# 07-MISC.net
KiCad netlist of a schematic drawn in Altium Designer
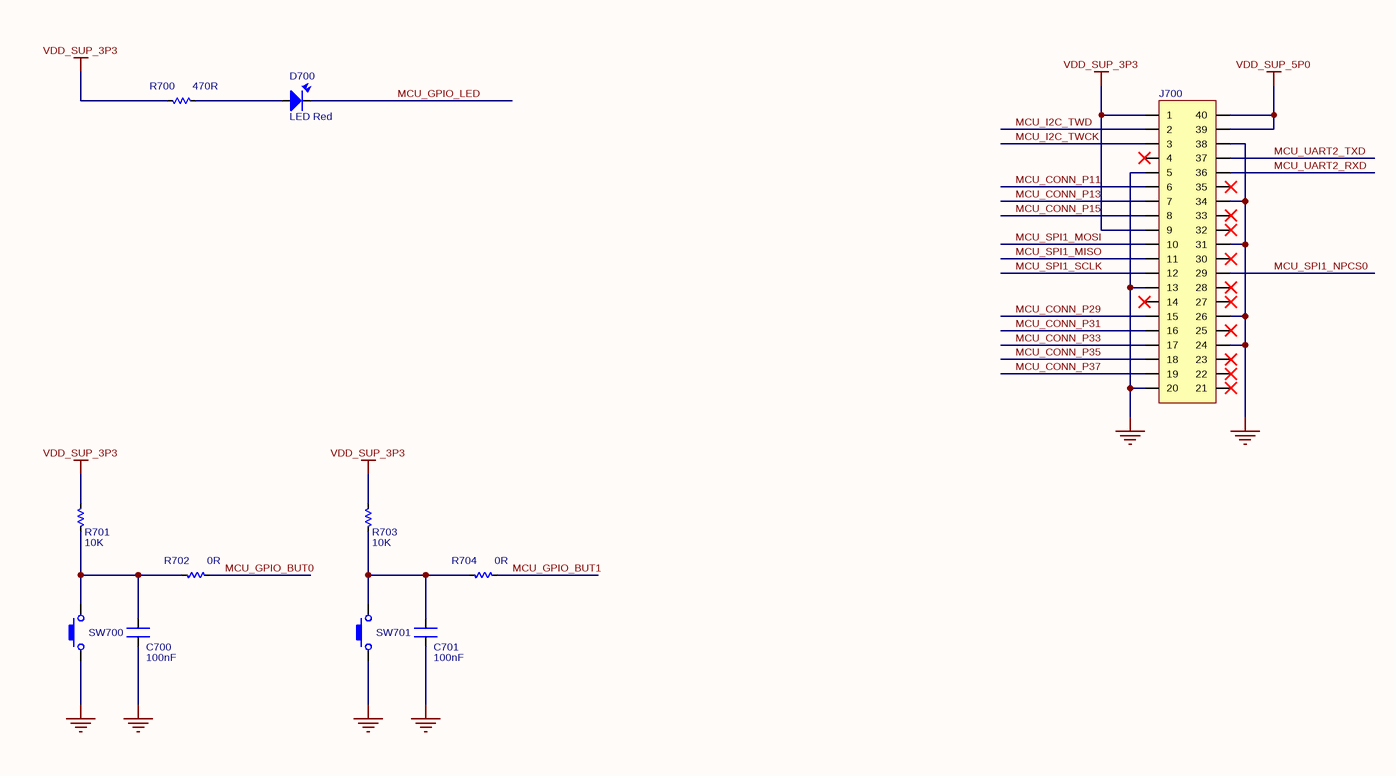
[diagram p0: 07-MISC.SchDoc]

(export (version "E")
  (design (tool "Eeschema 10.0.6"))
  (components
    (comp (ref "C700")
      (value "100nF")
      (footprint "CN-SMD-0603")
      (description "Ceramic Capacitor SMD 0603 100nF ±20% 10V")
      (fields (field (name "Comment") "Capacitor"))
      (libsource (lib "AS50") (part "Cap"))
    )
    (comp (ref "C701")
      (value "100nF")
      (footprint "CN-SMD-0603")
      (description "Ceramic Capacitor SMD 0603 100nF ±20% 10V")
      (fields (field (name "Comment") "Capacitor"))
      (libsource (lib "AS50") (part "Cap"))
    )
    (comp (ref "D700")
      (value "LED Red")
      (footprint "LED-SMD-0805-RED")
      (description "Light Emitting Diode SMD 0805 red color")
      (libsource (lib "AS50") (part "LED"))
    )
    (comp (ref "J700")
      (value "JP20x2")
      (footprint "JP20-D2T")
      (description "Double 20-pin jumper")
      (libsource (lib "AS50") (part "JP20x2"))
    )
    (comp (ref "R700")
      (value "470R")
      (footprint "RES-SMD-0603")
      (description "Resistor SMD 0603 470R 1% 0.1W")
      (fields (field (name "Comment") "Resistor"))
      (libsource (lib "AS50") (part "Res"))
    )
    (comp (ref "R701")
      (value "10K")
      (footprint "RES-SMD-0603")
      (description "Resistor SMD 0603 10K 1% 0.1W")
      (fields (field (name "Comment") "Resistor"))
      (libsource (lib "AS50") (part "Res"))
    )
    (comp (ref "R702")
      (value "0R")
      (footprint "RES-SMD-0603")
      (description "Resistor SMD 0603 0R 1% 0.1W")
      (fields (field (name "Comment") "Resistor"))
      (libsource (lib "AS50") (part "Res"))
    )
    (comp (ref "R703")
      (value "10K")
      (footprint "RES-SMD-0603")
      (description "Resistor SMD 0603 10K 1% 0.1W")
      (fields (field (name "Comment") "Resistor"))
      (libsource (lib "AS50") (part "Res"))
    )
    (comp (ref "R704")
      (value "0R")
      (footprint "RES-SMD-0603")
      (description "Resistor SMD 0603 0R 1% 0.1W")
      (fields (field (name "Comment") "Resistor"))
      (libsource (lib "AS50") (part "Res"))
    )
    (comp (ref "SW700")
      (value "SW2")
      (footprint "SW2-SMD-3x4x2M")
      (description "Switch 2-pin SMD 3x4x2mm")
      (libsource (lib "AS50") (part "SW2"))
    )
    (comp (ref "SW701")
      (value "SW2")
      (footprint "SW2-SMD-3x4x2M")
      (description "Switch 2-pin SMD 3x4x2mm")
      (libsource (lib "AS50") (part "SW2"))
    )
  )
  (nets
    (net (code "1") (name "/MCU_CONN_P11") (class "Default")
      (node (ref "J700") (pin "6") (pinfunction "6_6") (pintype "passive"))
    )
    (net (code "2") (name "/MCU_CONN_P13") (class "Default")
      (node (ref "J700") (pin "7") (pinfunction "7_7") (pintype "passive"))
    )
    (net (code "3") (name "/MCU_CONN_P15") (class "Default")
      (node (ref "J700") (pin "8") (pinfunction "8_8") (pintype "passive"))
    )
    (net (code "4") (name "/MCU_CONN_P29") (class "Default")
      (node (ref "J700") (pin "15") (pinfunction "15_15") (pintype "passive"))
    )
    (net (code "5") (name "/MCU_CONN_P31") (class "Default")
      (node (ref "J700") (pin "16") (pinfunction "16_16") (pintype "passive"))
    )
    (net (code "6") (name "/MCU_CONN_P33") (class "Default")
      (node (ref "J700") (pin "17") (pinfunction "17_17") (pintype "passive"))
    )
    (net (code "7") (name "/MCU_CONN_P35") (class "Default")
      (node (ref "J700") (pin "18") (pinfunction "18_18") (pintype "passive"))
    )
    (net (code "8") (name "/MCU_CONN_P37") (class "Default")
      (node (ref "J700") (pin "19") (pinfunction "19_19") (pintype "passive"))
    )
    (net (code "9") (name "/MCU_GPIO_BUT0") (class "Default")
      (node (ref "R702") (pin "2") (pinfunction "2_2") (pintype "passive"))
    )
    (net (code "10") (name "/MCU_GPIO_BUT1") (class "Default")
      (node (ref "R704") (pin "2") (pinfunction "2_2") (pintype "passive"))
    )
    (net (code "11") (name "/MCU_GPIO_LED") (class "Default")
      (node (ref "D700") (pin "2") (pinfunction "2_2") (pintype "passive"))
    )
    (net (code "12") (name "/MCU_I2C_TWCK") (class "Default")
      (node (ref "J700") (pin "3") (pinfunction "3_3") (pintype "passive"))
    )
    (net (code "13") (name "/MCU_I2C_TWD") (class "Default")
      (node (ref "J700") (pin "2") (pinfunction "2_2") (pintype "passive"))
    )
    (net (code "14") (name "/MCU_SPI1_MISO") (class "Default")
      (node (ref "J700") (pin "11") (pinfunction "11_11") (pintype "passive"))
    )
    (net (code "15") (name "/MCU_SPI1_MOSI") (class "Default")
      (node (ref "J700") (pin "10") (pinfunction "10_10") (pintype "passive"))
    )
    (net (code "16") (name "/MCU_SPI1_NPCS0") (class "Default")
      (node (ref "J700") (pin "29") (pinfunction "29_29") (pintype "passive"))
    )
    (net (code "17") (name "/MCU_SPI1_SCLK") (class "Default")
      (node (ref "J700") (pin "12") (pinfunction "12_12") (pintype "passive"))
    )
    (net (code "18") (name "/MCU_UART2_RXD") (class "Default")
      (node (ref "J700") (pin "36") (pinfunction "36_36") (pintype "passive"))
    )
    (net (code "19") (name "/MCU_UART2_TXD") (class "Default")
      (node (ref "J700") (pin "37") (pinfunction "37_37") (pintype "passive"))
    )
    (net (code "20") (name "GND") (class "Default")
      (node (ref "C700") (pin "1") (pinfunction "1_1") (pintype "passive"))
      (node (ref "C701") (pin "1") (pinfunction "1_1") (pintype "passive"))
      (node (ref "J700") (pin "13") (pinfunction "13_13") (pintype "passive"))
      (node (ref "J700") (pin "20") (pinfunction "20_20") (pintype "passive"))
      (node (ref "J700") (pin "24") (pinfunction "24_24") (pintype "passive"))
      (node (ref "J700") (pin "26") (pinfunction "26_26") (pintype "passive"))
      (node (ref "J700") (pin "31") (pinfunction "31_31") (pintype "passive"))
      (node (ref "J700") (pin "34") (pinfunction "34_34") (pintype "passive"))
      (node (ref "J700") (pin "38") (pinfunction "38_38") (pintype "passive"))
      (node (ref "J700") (pin "5") (pinfunction "5_5") (pintype "passive"))
      (node (ref "SW700") (pin "1") (pinfunction "1_1") (pintype "passive"))
      (node (ref "SW701") (pin "1") (pinfunction "1_1") (pintype "passive"))
    )
    (net (code "21") (name "Net-(C700-Pad2)") (class "Default")
      (node (ref "C700") (pin "2") (pinfunction "2_2") (pintype "passive"))
      (node (ref "R701") (pin "2") (pinfunction "2_2") (pintype "passive"))
      (node (ref "R702") (pin "1") (pinfunction "1_1") (pintype "passive"))
      (node (ref "SW700") (pin "2") (pinfunction "2_2") (pintype "passive"))
    )
    (net (code "22") (name "Net-(C701-Pad2)") (class "Default")
      (node (ref "C701") (pin "2") (pinfunction "2_2") (pintype "passive"))
      (node (ref "R703") (pin "2") (pinfunction "2_2") (pintype "passive"))
      (node (ref "R704") (pin "1") (pinfunction "1_1") (pintype "passive"))
      (node (ref "SW701") (pin "2") (pinfunction "2_2") (pintype "passive"))
    )
    (net (code "23") (name "Net-(D700-Pad1)") (class "Default")
      (node (ref "D700") (pin "1") (pinfunction "1_1") (pintype "passive"))
      (node (ref "R700") (pin "2") (pinfunction "2_2") (pintype "passive"))
    )
    (net (code "24") (name "VDD_SUP_3P3") (class "Default")
      (node (ref "J700") (pin "1") (pinfunction "1_1") (pintype "passive"))
      (node (ref "J700") (pin "9") (pinfunction "9_9") (pintype "passive"))
      (node (ref "R700") (pin "1") (pinfunction "1_1") (pintype "passive"))
      (node (ref "R701") (pin "1") (pinfunction "1_1") (pintype "passive"))
      (node (ref "R703") (pin "1") (pinfunction "1_1") (pintype "passive"))
    )
    (net (code "25") (name "VDD_SUP_5P0") (class "Default")
      (node (ref "J700") (pin "39") (pinfunction "39_39") (pintype "passive"))
      (node (ref "J700") (pin "40") (pinfunction "40_40") (pintype "passive"))
    )
    (net (code "26") (name "unconnected-(J700-Pad4)") (class "Default")
      (node (ref "J700") (pin "4") (pinfunction "4_4") (pintype "passive+no_connect"))
    )
    (net (code "27") (name "unconnected-(J700-Pad14)") (class "Default")
      (node (ref "J700") (pin "14") (pinfunction "14_14") (pintype "passive+no_connect"))
    )
    (net (code "28") (name "unconnected-(J700-Pad21)") (class "Default")
      (node (ref "J700") (pin "21") (pinfunction "21_21") (pintype "passive+no_connect"))
    )
    (net (code "29") (name "unconnected-(J700-Pad22)") (class "Default")
      (node (ref "J700") (pin "22") (pinfunction "22_22") (pintype "passive+no_connect"))
    )
    (net (code "30") (name "unconnected-(J700-Pad23)") (class "Default")
      (node (ref "J700") (pin "23") (pinfunction "23_23") (pintype "passive+no_connect"))
    )
    (net (code "31") (name "unconnected-(J700-Pad25)") (class "Default")
      (node (ref "J700") (pin "25") (pinfunction "25_25") (pintype "passive+no_connect"))
    )
    (net (code "32") (name "unconnected-(J700-Pad27)") (class "Default")
      (node (ref "J700") (pin "27") (pinfunction "27_27") (pintype "passive+no_connect"))
    )
    (net (code "33") (name "unconnected-(J700-Pad28)") (class "Default")
      (node (ref "J700") (pin "28") (pinfunction "28_28") (pintype "passive+no_connect"))
    )
    (net (code "34") (name "unconnected-(J700-Pad30)") (class "Default")
      (node (ref "J700") (pin "30") (pinfunction "30_30") (pintype "passive+no_connect"))
    )
    (net (code "35") (name "unconnected-(J700-Pad32)") (class "Default")
      (node (ref "J700") (pin "32") (pinfunction "32_32") (pintype "passive+no_connect"))
    )
    (net (code "36") (name "unconnected-(J700-Pad33)") (class "Default")
      (node (ref "J700") (pin "33") (pinfunction "33_33") (pintype "passive+no_connect"))
    )
    (net (code "37") (name "unconnected-(J700-Pad35)") (class "Default")
      (node (ref "J700") (pin "35") (pinfunction "35_35") (pintype "passive+no_connect"))
    )
  )
)
